# CF_ALIM.net
KiCad netlist of a schematic drawn in Altium Designer
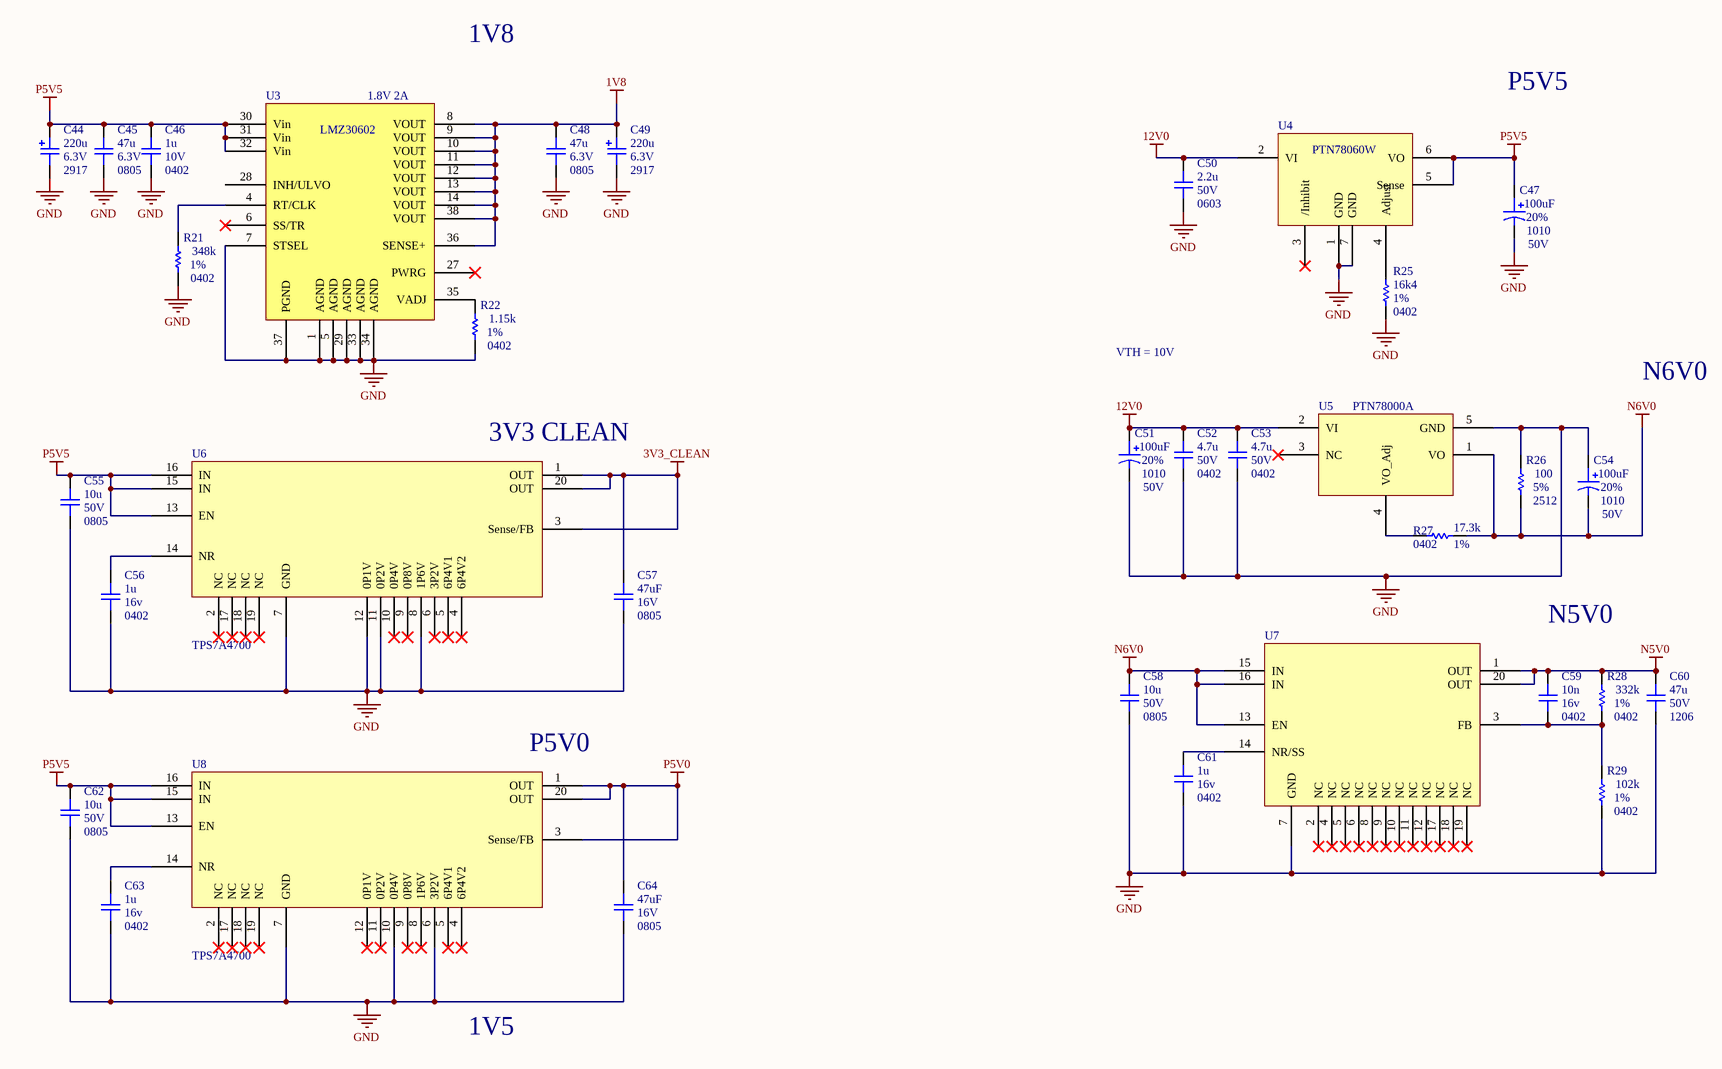
[diagram p0: CF_ALIM.SchDoc]

(export (version "E")
  (design (tool "Eeschema 10.0.6"))
  (components
    (comp (ref "C44")
      (value "220u")
      (footprint "CAP_TAN_2917(D)")
      (description "CAP - TANTALUM - 2917")
      (fields
        (field (name "VOLTAGE") "6.3V")
        (field (name "PACKAGE") "2917")
        (field (name "Comment") "CAP - TANTALUM - CASE D")
        (field (name "CREATEDBY") "Jonathan Bouchard")
      )
      (libsource (lib "S7CAS_Lib2019_REV1_00") (part "CAP_TANT_2917(D)"))
    )
    (comp (ref "C45")
      (value "47u")
      (footprint "CAP_0805")
      (description "CAP - 0805")
      (fields
        (field (name "VOLTAGE") "6.3V")
        (field (name "PACKAGE") "0805")
        (field (name "CREATEDBY") "Jonathan Bouchard")
      )
      (libsource (lib "S7CAS_Lib2019_REV1_00") (part "CAP - 0805"))
    )
    (comp (ref "C46")
      (value "1u")
      (footprint "CAP_0402")
      (description "CAP - 0402")
      (fields
        (field (name "VOLTAGE") "10V")
        (field (name "PACKAGE") "0402")
        (field (name "CREATEDBY") "Jonathan Bouchard")
      )
      (libsource (lib "S7CAS_Lib2019_REV1_00") (part "CAP - 0402"))
    )
    (comp (ref "C47")
      (value "100uF")
      (footprint "CapacitorE")
      (description "CAP - ALU 100uF 20% 50V - 1010")
      (fields
        (field (name "MFG") "Vishay Dale")
        (field (name "MFG PART NUMBER") "MAL215099101E3")
        (field (name "VOLTAGE") "50V")
        (field (name "PACKAGE") "1010")
        (field (name "PRECISION") "20%")
        (field (name "CREATEDBY") "Jonathan Bouchard")
      )
      (libsource (lib "S7CAS_Lib2019_REV1_00") (part "CAP_ALU_MAL215099101E3"))
    )
    (comp (ref "C48")
      (value "47u")
      (footprint "CAP_0805")
      (description "CAP - 0805")
      (fields
        (field (name "VOLTAGE") "6.3V")
        (field (name "PACKAGE") "0805")
        (field (name "CREATEDBY") "Jonathan Bouchard")
      )
      (libsource (lib "S7CAS_Lib2019_REV1_00") (part "CAP - 0805"))
    )
    (comp (ref "C49")
      (value "220u")
      (footprint "CAP_TAN_2917(D)")
      (description "CAP - TANTALUM - 2917")
      (fields
        (field (name "VOLTAGE") "6.3V")
        (field (name "PACKAGE") "2917")
        (field (name "Comment") "CAP - TANTALUM - CASE D")
        (field (name "CREATEDBY") "Jonathan Bouchard")
      )
      (libsource (lib "S7CAS_Lib2019_REV1_00") (part "CAP_TANT_2917(D)"))
    )
    (comp (ref "C50")
      (value "2.2u")
      (footprint "CAP_0603")
      (description "CAP - 0603")
      (fields
        (field (name "VOLTAGE") "50V")
        (field (name "PACKAGE") "0603")
        (field (name "CREATEDBY") "Jonathan Bouchard")
      )
      (libsource (lib "S7CAS_Lib2019_REV1_00") (part "CAP - 0603"))
    )
    (comp (ref "C51")
      (value "100uF")
      (footprint "CapacitorE")
      (description "CAP - ALU 100uF 20% 50V - 1010")
      (fields
        (field (name "MFG") "Vishay Dale")
        (field (name "MFG PART NUMBER") "MAL215099101E3")
        (field (name "VOLTAGE") "50V")
        (field (name "PACKAGE") "1010")
        (field (name "PRECISION") "20%")
        (field (name "CREATEDBY") "Jonathan Bouchard")
      )
      (libsource (lib "S7CAS_Lib2019_REV1_00") (part "CAP_ALU_MAL215099101E3"))
    )
    (comp (ref "C52")
      (value "4.7u")
      (footprint "CAP_0402")
      (description "CAP - 0402")
      (fields
        (field (name "VOLTAGE") "50V")
        (field (name "PACKAGE") "0402")
        (field (name "CREATEDBY") "Jonathan Bouchard")
      )
      (libsource (lib "S7CAS_Lib2019_REV1_00") (part "CAP - 0402"))
    )
    (comp (ref "C53")
      (value "4.7u")
      (footprint "CAP_0402")
      (description "CAP - 0402")
      (fields
        (field (name "VOLTAGE") "50V")
        (field (name "PACKAGE") "0402")
        (field (name "CREATEDBY") "Jonathan Bouchard")
      )
      (libsource (lib "S7CAS_Lib2019_REV1_00") (part "CAP - 0402"))
    )
    (comp (ref "C54")
      (value "100uF")
      (footprint "CapacitorE")
      (description "CAP - ALU 100uF 20% 50V - 1010")
      (fields
        (field (name "MFG") "Vishay Dale")
        (field (name "MFG PART NUMBER") "MAL215099101E3")
        (field (name "VOLTAGE") "50V")
        (field (name "PACKAGE") "1010")
        (field (name "PRECISION") "20%")
        (field (name "CREATEDBY") "Jonathan Bouchard")
      )
      (libsource (lib "S7CAS_Lib2019_REV1_00") (part "CAP_ALU_MAL215099101E3"))
    )
    (comp (ref "C55")
      (value "10u")
      (footprint "CAP_0402")
      (description "CAP - 0402")
      (fields
        (field (name "VOLTAGE") "50V")
        (field (name "PACKAGE") "0805")
        (field (name "CREATEDBY") "Jonathan Bouchard")
      )
      (libsource (lib "S7CAS_Lib2019_REV1_00") (part "CAP - 0402"))
    )
    (comp (ref "C56")
      (value "1u")
      (footprint "CAP_0402")
      (description "CAP - 0402")
      (fields
        (field (name "VOLTAGE") "16v")
        (field (name "PACKAGE") "0402")
        (field (name "CREATEDBY") "Jonathan Bouchard")
      )
      (libsource (lib "S7CAS_Lib2019_REV1_00") (part "CAP - 0402"))
    )
    (comp (ref "C57")
      (value "47uF")
      (footprint "CAP_0805")
      (description "CAP - 0805")
      (fields
        (field (name "VOLTAGE") "16V")
        (field (name "PACKAGE") "0805")
        (field (name "CREATEDBY") "Jonathan Bouchard")
      )
      (libsource (lib "S7CAS_Lib2019_REV1_00") (part "CAP - 0805"))
    )
    (comp (ref "C58")
      (value "10u")
      (footprint "CAP_0402")
      (description "CAP - 0402")
      (fields
        (field (name "VOLTAGE") "50V")
        (field (name "PACKAGE") "0805")
        (field (name "CREATEDBY") "Jonathan Bouchard")
      )
      (libsource (lib "S7CAS_Lib2019_REV1_00") (part "CAP - 0402"))
    )
    (comp (ref "C59")
      (value "10n")
      (footprint "CAP_0402")
      (description "CAP - 0402")
      (fields
        (field (name "VOLTAGE") "16v")
        (field (name "PACKAGE") "0402")
        (field (name "CREATEDBY") "Jonathan Bouchard")
      )
      (libsource (lib "S7CAS_Lib2019_REV1_00") (part "CAP - 0402"))
    )
    (comp (ref "C60")
      (value "47u")
      (footprint "CAP_1206")
      (description "CAP - 1206")
      (fields
        (field (name "VOLTAGE") "50V")
        (field (name "PACKAGE") "1206")
        (field (name "CREATEDBY") "Jonathan Bouchard")
      )
      (libsource (lib "S7CAS_Lib2019_REV1_00") (part "CAP - 1206"))
    )
    (comp (ref "C61")
      (value "1u")
      (footprint "CAP_0402")
      (description "CAP - 0402")
      (fields
        (field (name "VOLTAGE") "16v")
        (field (name "PACKAGE") "0402")
        (field (name "CREATEDBY") "Jonathan Bouchard")
      )
      (libsource (lib "S7CAS_Lib2019_REV1_00") (part "CAP - 0402"))
    )
    (comp (ref "C62")
      (value "10u")
      (footprint "CAP_0402")
      (description "CAP - 0402")
      (fields
        (field (name "VOLTAGE") "50V")
        (field (name "PACKAGE") "0805")
        (field (name "CREATEDBY") "Jonathan Bouchard")
      )
      (libsource (lib "S7CAS_Lib2019_REV1_00") (part "CAP - 0402"))
    )
    (comp (ref "C63")
      (value "1u")
      (footprint "CAP_0402")
      (description "CAP - 0402")
      (fields
        (field (name "VOLTAGE") "16v")
        (field (name "PACKAGE") "0402")
        (field (name "CREATEDBY") "Jonathan Bouchard")
      )
      (libsource (lib "S7CAS_Lib2019_REV1_00") (part "CAP - 0402"))
    )
    (comp (ref "C64")
      (value "47uF")
      (footprint "CAP_0805")
      (description "CAP - 0805")
      (fields
        (field (name "VOLTAGE") "16V")
        (field (name "PACKAGE") "0805")
        (field (name "CREATEDBY") "Jonathan Bouchard")
      )
      (libsource (lib "S7CAS_Lib2019_REV1_00") (part "CAP - 0805"))
    )
    (comp (ref "R21")
      (value "348k")
      (footprint "RES_0402")
      (description "RES - 0402")
      (fields
        (field (name "VOLTAGE") "50V")
        (field (name "POWER") "1/16W")
        (field (name "PACKAGE") "0402")
        (field (name "PRECISION") "1%")
        (field (name "CREATEDBY") "Jonathan Bouchard")
      )
      (libsource (lib "S7CAS_Lib2019_REV1_00") (part "RES - 0402"))
    )
    (comp (ref "R22")
      (value "1.15k")
      (footprint "RES_0402")
      (description "RES - 0402")
      (fields
        (field (name "VOLTAGE") "50V")
        (field (name "POWER") "1/16W")
        (field (name "PACKAGE") "0402")
        (field (name "PRECISION") "1%")
        (field (name "CREATEDBY") "Jonathan Bouchard")
      )
      (libsource (lib "S7CAS_Lib2019_REV1_00") (part "RES - 0402"))
    )
    (comp (ref "R25")
      (value "16k4")
      (footprint "RES_0402")
      (description "RES - 0402")
      (fields
        (field (name "VOLTAGE") "50V")
        (field (name "POWER") "1/16W")
        (field (name "PACKAGE") "0402")
        (field (name "PRECISION") "1%")
        (field (name "CREATEDBY") "Jonathan Bouchard")
      )
      (libsource (lib "S7CAS_Lib2019_REV1_00") (part "RES - 0402"))
    )
    (comp (ref "R26")
      (value "100")
      (footprint "C2512")
      (description "RES - 0402")
      (fields
        (field (name "VOLTAGE") "50V")
        (field (name "POWER") "1/16W")
        (field (name "PACKAGE") "2512")
        (field (name "PRECISION") "5%")
        (field (name "CREATEDBY") "Jonathan Bouchard")
      )
      (libsource (lib "S7CAS_Lib2019_REV1_00") (part "RES - 0402"))
    )
    (comp (ref "R27")
      (value "17.3k")
      (footprint "RES_0402")
      (description "RES - 0402")
      (fields
        (field (name "VOLTAGE") "50V")
        (field (name "POWER") "1/16W")
        (field (name "PACKAGE") "0402")
        (field (name "PRECISION") "1%")
        (field (name "CREATEDBY") "Jonathan Bouchard")
      )
      (libsource (lib "S7CAS_Lib2019_REV1_00") (part "RES - 0402"))
    )
    (comp (ref "R28")
      (value "332k")
      (footprint "RES_0402")
      (description "RES - 0402")
      (fields
        (field (name "VOLTAGE") "50V")
        (field (name "POWER") "1/16W")
        (field (name "PACKAGE") "0402")
        (field (name "PRECISION") "1%")
        (field (name "CREATEDBY") "Jonathan Bouchard")
      )
      (libsource (lib "S7CAS_Lib2019_REV1_00") (part "RES - 0402"))
    )
    (comp (ref "R29")
      (value "102k")
      (footprint "RES_0402")
      (description "RES - 0402")
      (fields
        (field (name "VOLTAGE") "50V")
        (field (name "POWER") "1/16W")
        (field (name "PACKAGE") "0402")
        (field (name "PRECISION") "1%")
        (field (name "CREATEDBY") "Jonathan Bouchard")
      )
      (libsource (lib "S7CAS_Lib2019_REV1_00") (part "RES - 0402"))
    )
    (comp (ref "U3")
      (value "LMZ30602")
      (footprint "RKG39 QFN")
      (description "2A Power Module")
      (libsource (lib "Custom") (part "LMZ3602"))
    )
    (comp (ref "U4")
      (value "PTN78060W")
      (footprint "EUW")
      (description "Wide input volate regulator")
      (libsource (lib "Custom") (part "PTN78060W"))
    )
    (comp (ref "U5")
      (value "PTN78000A")
      (footprint "PTN78000A")
      (libsource (lib "PTN78000A") (part "PTN78000A"))
    )
    (comp (ref "U6")
      (value "TPS7A4700")
      (footprint "TPS7A4700")
      (libsource (lib "TPS7A4700") (part "TPS7A4700"))
    )
    (comp (ref "U7") (value "~") (footprint "TPS7A4700") (libsource (lib "TPS7A33") (part "TPS7A33")))
    (comp (ref "U8")
      (value "TPS7A4700")
      (footprint "TPS7A4700")
      (libsource (lib "TPS7A4700") (part "TPS7A4700"))
    )
  )
  (nets
    (net (code "1") (name "1V8") (class "Default")
      (node (ref "C48") (pin "2") (pinfunction "2_2") (pintype "passive"))
      (node (ref "C49") (pin "2") (pinfunction "2_2") (pintype "passive"))
      (node (ref "U3") (pin "10") (pinfunction "VOUT_10") (pintype "passive"))
      (node (ref "U3") (pin "11") (pinfunction "VOUT_11") (pintype "passive"))
      (node (ref "U3") (pin "12") (pinfunction "VOUT_12") (pintype "passive"))
      (node (ref "U3") (pin "13") (pinfunction "VOUT_13") (pintype "passive"))
      (node (ref "U3") (pin "14") (pinfunction "VOUT_14") (pintype "passive"))
      (node (ref "U3") (pin "36") (pinfunction "SENSE+_36") (pintype "passive"))
      (node (ref "U3") (pin "38") (pinfunction "VOUT_38") (pintype "passive"))
      (node (ref "U3") (pin "8") (pinfunction "VOUT_8") (pintype "passive"))
      (node (ref "U3") (pin "9") (pinfunction "VOUT_9") (pintype "passive"))
    )
    (net (code "2") (name "3V3_CLEAN") (class "Default")
      (node (ref "C57") (pin "2") (pinfunction "2_2") (pintype "passive"))
      (node (ref "U6") (pin "1") (pinfunction "OUT_1") (pintype "passive"))
      (node (ref "U6") (pin "20") (pinfunction "OUT_20") (pintype "passive"))
      (node (ref "U6") (pin "3") (pinfunction "Sense/FB_3") (pintype "passive"))
    )
    (net (code "3") (name "12V0") (class "Default")
      (node (ref "C50") (pin "2") (pinfunction "2_2") (pintype "passive"))
      (node (ref "C51") (pin "1") (pinfunction "1_1") (pintype "passive"))
      (node (ref "C52") (pin "2") (pinfunction "2_2") (pintype "passive"))
      (node (ref "C53") (pin "2") (pinfunction "2_2") (pintype "passive"))
      (node (ref "U4") (pin "2") (pinfunction "VI_2") (pintype "passive"))
      (node (ref "U5") (pin "2") (pinfunction "VI_2") (pintype "passive"))
    )
    (net (code "4") (name "GND") (class "Default")
      (node (ref "C44") (pin "1") (pinfunction "1_1") (pintype "passive"))
      (node (ref "C45") (pin "1") (pinfunction "1_1") (pintype "passive"))
      (node (ref "C46") (pin "1") (pinfunction "1_1") (pintype "passive"))
      (node (ref "C47") (pin "2") (pinfunction "2_2") (pintype "passive"))
      (node (ref "C48") (pin "1") (pinfunction "1_1") (pintype "passive"))
      (node (ref "C49") (pin "1") (pinfunction "1_1") (pintype "passive"))
      (node (ref "C50") (pin "1") (pinfunction "1_1") (pintype "passive"))
      (node (ref "C51") (pin "2") (pinfunction "2_2") (pintype "passive"))
      (node (ref "C52") (pin "1") (pinfunction "1_1") (pintype "passive"))
      (node (ref "C53") (pin "1") (pinfunction "1_1") (pintype "passive"))
      (node (ref "C54") (pin "1") (pinfunction "1_1") (pintype "passive"))
      (node (ref "C55") (pin "1") (pinfunction "1_1") (pintype "passive"))
      (node (ref "C56") (pin "1") (pinfunction "1_1") (pintype "passive"))
      (node (ref "C57") (pin "1") (pinfunction "1_1") (pintype "passive"))
      (node (ref "C58") (pin "1") (pinfunction "1_1") (pintype "passive"))
      (node (ref "C60") (pin "1") (pinfunction "1_1") (pintype "passive"))
      (node (ref "C61") (pin "1") (pinfunction "1_1") (pintype "passive"))
      (node (ref "C62") (pin "1") (pinfunction "1_1") (pintype "passive"))
      (node (ref "C63") (pin "1") (pinfunction "1_1") (pintype "passive"))
      (node (ref "C64") (pin "1") (pinfunction "1_1") (pintype "passive"))
      (node (ref "R21") (pin "1") (pinfunction "1_1") (pintype "passive"))
      (node (ref "R22") (pin "1") (pinfunction "1_1") (pintype "passive"))
      (node (ref "R25") (pin "1") (pinfunction "1_1") (pintype "passive"))
      (node (ref "R26") (pin "2") (pinfunction "2_2") (pintype "passive"))
      (node (ref "R29") (pin "1") (pinfunction "1_1") (pintype "passive"))
      (node (ref "U3") (pin "1") (pinfunction "AGND_1") (pintype "passive"))
      (node (ref "U3") (pin "29") (pinfunction "AGND_29") (pintype "passive"))
      (node (ref "U3") (pin "33") (pinfunction "AGND_33") (pintype "passive"))
      (node (ref "U3") (pin "34") (pinfunction "AGND_34") (pintype "passive"))
      (node (ref "U3") (pin "37") (pinfunction "PGND_37") (pintype "passive"))
      (node (ref "U3") (pin "5") (pinfunction "AGND_5") (pintype "passive"))
      (node (ref "U3") (pin "7") (pinfunction "STSEL_7") (pintype "passive"))
      (node (ref "U4") (pin "1") (pinfunction "GND_1") (pintype "passive"))
      (node (ref "U4") (pin "7") (pinfunction "GND_7") (pintype "passive"))
      (node (ref "U5") (pin "5") (pinfunction "GND_5") (pintype "passive"))
      (node (ref "U6") (pin "11") (pinfunction "0P2V_11") (pintype "passive"))
      (node (ref "U6") (pin "12") (pinfunction "0P1V_12") (pintype "passive"))
      (node (ref "U6") (pin "7") (pinfunction "GND_7") (pintype "passive"))
      (node (ref "U6") (pin "8") (pinfunction "1P6V_8") (pintype "passive"))
      (node (ref "U7") (pin "7") (pinfunction "GND_7") (pintype "passive"))
      (node (ref "U8") (pin "10") (pinfunction "0P4V_10") (pintype "passive"))
      (node (ref "U8") (pin "6") (pinfunction "3P2V_6") (pintype "passive"))
      (node (ref "U8") (pin "7") (pinfunction "GND_7") (pintype "passive"))
    )
    (net (code "5") (name "N5V0") (class "Default")
      (node (ref "C59") (pin "2") (pinfunction "2_2") (pintype "passive"))
      (node (ref "C60") (pin "2") (pinfunction "2_2") (pintype "passive"))
      (node (ref "R28") (pin "2") (pinfunction "2_2") (pintype "passive"))
      (node (ref "U7") (pin "1") (pinfunction "OUT_1") (pintype "passive"))
      (node (ref "U7") (pin "20") (pinfunction "OUT_20") (pintype "passive"))
    )
    (net (code "6") (name "N6V0") (class "Default")
      (node (ref "C54") (pin "2") (pinfunction "2_2") (pintype "passive"))
      (node (ref "C58") (pin "2") (pinfunction "2_2") (pintype "passive"))
      (node (ref "R26") (pin "1") (pinfunction "1_1") (pintype "passive"))
      (node (ref "R27") (pin "1") (pinfunction "1_1") (pintype "passive"))
      (node (ref "U5") (pin "1") (pinfunction "VO_1") (pintype "passive"))
      (node (ref "U7") (pin "13") (pinfunction "EN_13") (pintype "passive"))
      (node (ref "U7") (pin "15") (pinfunction "IN_15") (pintype "passive"))
      (node (ref "U7") (pin "16") (pinfunction "IN_16") (pintype "passive"))
    )
    (net (code "7") (name "Net-(U3-RT{slash}CLK)") (class "Default")
      (node (ref "R21") (pin "2") (pinfunction "2_2") (pintype "passive"))
      (node (ref "U3") (pin "4") (pinfunction "RT/CLK_4") (pintype "passive"))
    )
    (net (code "8") (name "Net-(U3-VADJ)") (class "Default")
      (node (ref "R22") (pin "2") (pinfunction "2_2") (pintype "passive"))
      (node (ref "U3") (pin "35") (pinfunction "VADJ_35") (pintype "passive"))
    )
    (net (code "9") (name "Net-(U4-Adjust)") (class "Default")
      (node (ref "R25") (pin "2") (pinfunction "2_2") (pintype "passive"))
      (node (ref "U4") (pin "4") (pinfunction "Adjust_4") (pintype "passive"))
    )
    (net (code "10") (name "Net-(U5-VO_Adj)") (class "Default")
      (node (ref "R27") (pin "2") (pinfunction "2_2") (pintype "passive"))
      (node (ref "U5") (pin "4") (pinfunction "VO_Adj_4") (pintype "passive"))
    )
    (net (code "11") (name "Net-(U6-NR)") (class "Default")
      (node (ref "C56") (pin "2") (pinfunction "2_2") (pintype "passive"))
      (node (ref "U6") (pin "14") (pinfunction "NR_14") (pintype "passive"))
    )
    (net (code "12") (name "Net-(U7-FB)") (class "Default")
      (node (ref "C59") (pin "1") (pinfunction "1_1") (pintype "passive"))
      (node (ref "R28") (pin "1") (pinfunction "1_1") (pintype "passive"))
      (node (ref "R29") (pin "2") (pinfunction "2_2") (pintype "passive"))
      (node (ref "U7") (pin "3") (pinfunction "FB_3") (pintype "passive"))
    )
    (net (code "13") (name "Net-(U7-NR{slash}SS)") (class "Default")
      (node (ref "C61") (pin "2") (pinfunction "2_2") (pintype "passive"))
      (node (ref "U7") (pin "14") (pinfunction "NR/SS_14") (pintype "passive"))
    )
    (net (code "14") (name "Net-(U8-NR)") (class "Default")
      (node (ref "C63") (pin "2") (pinfunction "2_2") (pintype "passive"))
      (node (ref "U8") (pin "14") (pinfunction "NR_14") (pintype "passive"))
    )
    (net (code "15") (name "P5V0") (class "Default")
      (node (ref "C64") (pin "2") (pinfunction "2_2") (pintype "passive"))
      (node (ref "U8") (pin "1") (pinfunction "OUT_1") (pintype "passive"))
      (node (ref "U8") (pin "20") (pinfunction "OUT_20") (pintype "passive"))
      (node (ref "U8") (pin "3") (pinfunction "Sense/FB_3") (pintype "passive"))
    )
    (net (code "16") (name "P5V5") (class "Default")
      (node (ref "C44") (pin "2") (pinfunction "2_2") (pintype "passive"))
      (node (ref "C45") (pin "2") (pinfunction "2_2") (pintype "passive"))
      (node (ref "C46") (pin "2") (pinfunction "2_2") (pintype "passive"))
      (node (ref "C47") (pin "1") (pinfunction "1_1") (pintype "passive"))
      (node (ref "C55") (pin "2") (pinfunction "2_2") (pintype "passive"))
      (node (ref "C62") (pin "2") (pinfunction "2_2") (pintype "passive"))
      (node (ref "U3") (pin "30") (pinfunction "Vin_30") (pintype "passive"))
      (node (ref "U3") (pin "31") (pinfunction "Vin_31") (pintype "passive"))
      (node (ref "U3") (pin "32") (pinfunction "Vin_32") (pintype "passive"))
      (node (ref "U4") (pin "5") (pinfunction "Sense_5") (pintype "passive"))
      (node (ref "U4") (pin "6") (pinfunction "VO_6") (pintype "passive"))
      (node (ref "U6") (pin "13") (pinfunction "EN_13") (pintype "passive"))
      (node (ref "U6") (pin "15") (pinfunction "IN_15") (pintype "passive"))
      (node (ref "U6") (pin "16") (pinfunction "IN_16") (pintype "passive"))
      (node (ref "U8") (pin "13") (pinfunction "EN_13") (pintype "passive"))
      (node (ref "U8") (pin "15") (pinfunction "IN_15") (pintype "passive"))
      (node (ref "U8") (pin "16") (pinfunction "IN_16") (pintype "passive"))
    )
    (net (code "17") (name "unconnected-(U3-INH{slash}ULVO-Pad28)") (class "Default")
      (node (ref "U3") (pin "28") (pinfunction "INH/ULVO_28") (pintype "passive"))
    )
    (net (code "18") (name "unconnected-(U3-PWRG-Pad27)") (class "Default")
      (node (ref "U3") (pin "27") (pinfunction "PWRG_27") (pintype "passive+no_connect"))
    )
    (net (code "19") (name "unconnected-(U3-SS{slash}TR-Pad6)") (class "Default")
      (node (ref "U3") (pin "6") (pinfunction "SS/TR_6") (pintype "passive+no_connect"))
    )
    (net (code "20") (name "unconnected-(U4-{slash}Inhibit-Pad3)") (class "Default")
      (node (ref "U4") (pin "3") (pinfunction "/Inhibit_3") (pintype "passive+no_connect"))
    )
    (net (code "21") (name "unconnected-(U5-NC-Pad3)") (class "Default")
      (node (ref "U5") (pin "3") (pinfunction "NC_3") (pintype "passive+no_connect"))
    )
    (net (code "22") (name "unconnected-(U6-0P4V-Pad10)") (class "Default")
      (node (ref "U6") (pin "10") (pinfunction "0P4V_10") (pintype "passive+no_connect"))
    )
    (net (code "23") (name "unconnected-(U6-0P8V-Pad9)") (class "Default")
      (node (ref "U6") (pin "9") (pinfunction "0P8V_9") (pintype "passive+no_connect"))
    )
    (net (code "24") (name "unconnected-(U6-3P2V-Pad6)") (class "Default")
      (node (ref "U6") (pin "6") (pinfunction "3P2V_6") (pintype "passive+no_connect"))
    )
    (net (code "25") (name "unconnected-(U6-6P4V1-Pad5)") (class "Default")
      (node (ref "U6") (pin "5") (pinfunction "6P4V1_5") (pintype "passive+no_connect"))
    )
    (net (code "26") (name "unconnected-(U6-6P4V2-Pad4)") (class "Default")
      (node (ref "U6") (pin "4") (pinfunction "6P4V2_4") (pintype "passive+no_connect"))
    )
    (net (code "27") (name "unconnected-(U6-NC-Pad2)") (class "Default")
      (node (ref "U6") (pin "2") (pinfunction "NC_2") (pintype "passive+no_connect"))
    )
    (net (code "28") (name "unconnected-(U6-NC-Pad17)") (class "Default")
      (node (ref "U6") (pin "17") (pinfunction "NC_17") (pintype "passive+no_connect"))
    )
    (net (code "29") (name "unconnected-(U6-NC-Pad18)") (class "Default")
      (node (ref "U6") (pin "18") (pinfunction "NC_18") (pintype "passive+no_connect"))
    )
    (net (code "30") (name "unconnected-(U6-NC-Pad19)") (class "Default")
      (node (ref "U6") (pin "19") (pinfunction "NC_19") (pintype "passive+no_connect"))
    )
    (net (code "31") (name "unconnected-(U7-NC-Pad2)") (class "Default")
      (node (ref "U7") (pin "2") (pinfunction "NC_2") (pintype "passive+no_connect"))
    )
    (net (code "32") (name "unconnected-(U7-NC-Pad4)") (class "Default")
      (node (ref "U7") (pin "4") (pinfunction "NC_4") (pintype "passive+no_connect"))
    )
    (net (code "33") (name "unconnected-(U7-NC-Pad5)") (class "Default")
      (node (ref "U7") (pin "5") (pinfunction "NC_5") (pintype "passive+no_connect"))
    )
    (net (code "34") (name "unconnected-(U7-NC-Pad6)") (class "Default")
      (node (ref "U7") (pin "6") (pinfunction "NC_6") (pintype "passive+no_connect"))
    )
    (net (code "35") (name "unconnected-(U7-NC-Pad8)") (class "Default")
      (node (ref "U7") (pin "8") (pinfunction "NC_8") (pintype "passive+no_connect"))
    )
    (net (code "36") (name "unconnected-(U7-NC-Pad9)") (class "Default")
      (node (ref "U7") (pin "9") (pinfunction "NC_9") (pintype "passive+no_connect"))
    )
    (net (code "37") (name "unconnected-(U7-NC-Pad10)") (class "Default")
      (node (ref "U7") (pin "10") (pinfunction "NC_10") (pintype "passive+no_connect"))
    )
    (net (code "38") (name "unconnected-(U7-NC-Pad11)") (class "Default")
      (node (ref "U7") (pin "11") (pinfunction "NC_11") (pintype "passive+no_connect"))
    )
    (net (code "39") (name "unconnected-(U7-NC-Pad12)") (class "Default")
      (node (ref "U7") (pin "12") (pinfunction "NC_12") (pintype "passive+no_connect"))
    )
    (net (code "40") (name "unconnected-(U7-NC-Pad17)") (class "Default")
      (node (ref "U7") (pin "17") (pinfunction "NC_17") (pintype "passive+no_connect"))
    )
    (net (code "41") (name "unconnected-(U7-NC-Pad18)") (class "Default")
      (node (ref "U7") (pin "18") (pinfunction "NC_18") (pintype "passive+no_connect"))
    )
    (net (code "42") (name "unconnected-(U7-NC-Pad19)") (class "Default")
      (node (ref "U7") (pin "19") (pinfunction "NC_19") (pintype "passive+no_connect"))
    )
    (net (code "43") (name "unconnected-(U8-0P1V-Pad12)") (class "Default")
      (node (ref "U8") (pin "12") (pinfunction "0P1V_12") (pintype "passive+no_connect"))
    )
    (net (code "44") (name "unconnected-(U8-0P2V-Pad11)") (class "Default")
      (node (ref "U8") (pin "11") (pinfunction "0P2V_11") (pintype "passive+no_connect"))
    )
    (net (code "45") (name "unconnected-(U8-0P8V-Pad9)") (class "Default")
      (node (ref "U8") (pin "9") (pinfunction "0P8V_9") (pintype "passive+no_connect"))
    )
    (net (code "46") (name "unconnected-(U8-1P6V-Pad8)") (class "Default")
      (node (ref "U8") (pin "8") (pinfunction "1P6V_8") (pintype "passive+no_connect"))
    )
    (net (code "47") (name "unconnected-(U8-6P4V1-Pad5)") (class "Default")
      (node (ref "U8") (pin "5") (pinfunction "6P4V1_5") (pintype "passive+no_connect"))
    )
    (net (code "48") (name "unconnected-(U8-6P4V2-Pad4)") (class "Default")
      (node (ref "U8") (pin "4") (pinfunction "6P4V2_4") (pintype "passive+no_connect"))
    )
    (net (code "49") (name "unconnected-(U8-NC-Pad2)") (class "Default")
      (node (ref "U8") (pin "2") (pinfunction "NC_2") (pintype "passive+no_connect"))
    )
    (net (code "50") (name "unconnected-(U8-NC-Pad17)") (class "Default")
      (node (ref "U8") (pin "17") (pinfunction "NC_17") (pintype "passive+no_connect"))
    )
    (net (code "51") (name "unconnected-(U8-NC-Pad18)") (class "Default")
      (node (ref "U8") (pin "18") (pinfunction "NC_18") (pintype "passive+no_connect"))
    )
    (net (code "52") (name "unconnected-(U8-NC-Pad19)") (class "Default")
      (node (ref "U8") (pin "19") (pinfunction "NC_19") (pintype "passive+no_connect"))
    )
  )
)
